# 04_2_Thermocouple_Handling_01.net
KiCad netlist of a schematic drawn in Altium Designer
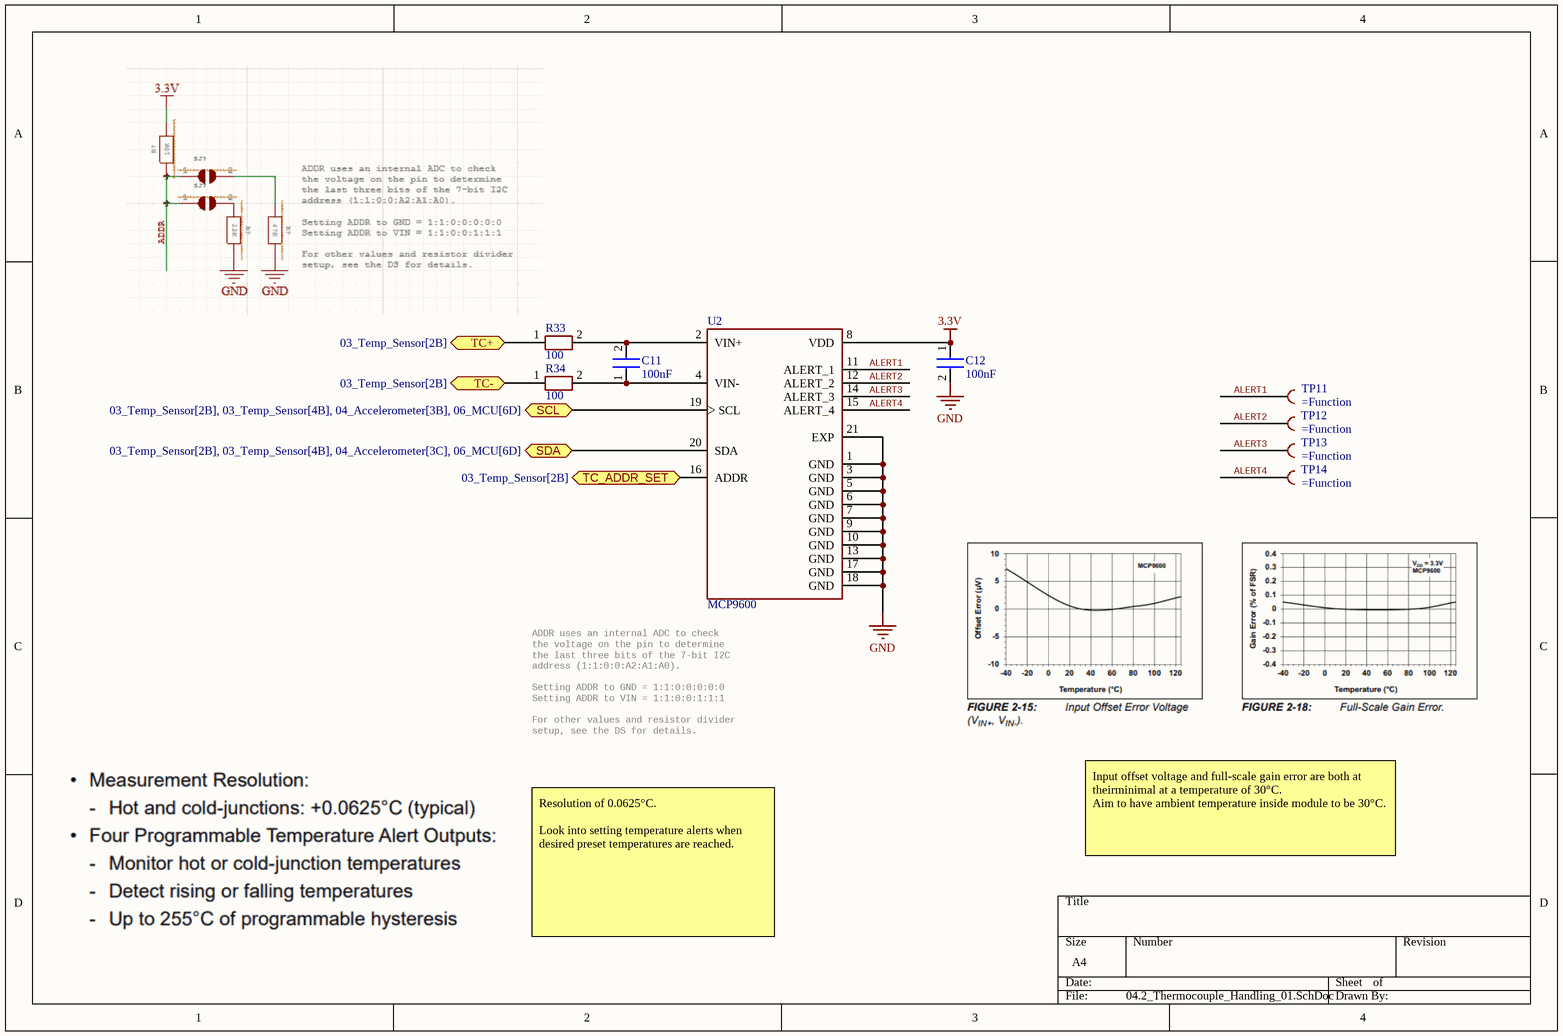
[diagram p0: 04.2_Thermocouple_Handling_01.SchDoc]

(export (version "E")
  (design (tool "Eeschema 10.0.6"))
  (components
    (comp (ref "C11")
      (value "100nF")
      (footprint "CAPC2012X94N")
      (description "Capacitor")
      (fields (field (name "MANUFACTURER_PART_NUMBER") "08055C104KAZ2A"))
      (libsource (lib "BraaiBuddyPCB_Schematic_Library") (part "CAP CER 100nF 0805 SMD"))
    )
    (comp (ref "C12")
      (value "100nF")
      (footprint "CAPC2012X94N")
      (description "Capacitor")
      (fields (field (name "MANUFACTURER_PART_NUMBER") "08055C104KAZ2A"))
      (libsource (lib "BraaiBuddyPCB_Schematic_Library") (part "CAP CER 100nF 0805 SMD"))
    )
    (comp (ref "R33")
      (value "100")
      (footprint "RESC2012X60N")
      (description "Resistor")
      (fields (field (name "MANUFACTURER_PART_NUMBER") "1623096-1"))
      (libsource (lib "BraaiBuddyPCB_Schematic_Library") (part "RES 100 0805 SMD"))
    )
    (comp (ref "R34")
      (value "100")
      (footprint "RESC2012X60N")
      (description "Resistor")
      (fields (field (name "MANUFACTURER_PART_NUMBER") "1623096-1"))
      (libsource (lib "BraaiBuddyPCB_Schematic_Library") (part "RES 100 0805 SMD"))
    )
    (comp (ref "TP11")
      (value "~")
      (footprint "TP_Pad_TH_1.2P_0.6H")
      (description "TP 1.5mm PAD")
      (libsource (lib "BraaiBuddyPCB_Schematic_Library") (part "TP 1.5mm PAD"))
    )
    (comp (ref "TP12")
      (value "~")
      (footprint "TP_Pad_TH_1.2P_0.6H")
      (description "TP 1.5mm PAD")
      (libsource (lib "BraaiBuddyPCB_Schematic_Library") (part "TP 1.5mm PAD"))
    )
    (comp (ref "TP13")
      (value "~")
      (footprint "TP_Pad_TH_1.2P_0.6H")
      (description "TP 1.5mm PAD")
      (libsource (lib "BraaiBuddyPCB_Schematic_Library") (part "TP 1.5mm PAD"))
    )
    (comp (ref "TP14")
      (value "~")
      (footprint "TP_Pad_TH_1.2P_0.6H")
      (description "TP 1.5mm PAD")
      (libsource (lib "BraaiBuddyPCB_Schematic_Library") (part "TP 1.5mm PAD"))
    )
    (comp (ref "U2")
      (value "MCP9600")
      (footprint "QFN65P500X500X100-21N")
      (description "MCP9600 Series Thermocouple Electromotive Force to Â±1.5Â°C Converter - VQFN-2")
      (fields (field (name "MANUFACTURER_PART_NUMBER") "MCP9600-E/MX"))
      (libsource (lib "BraaiBuddyPCB_Schematic_Library") (part "IC TYPE_K AMP I2Q MCP9600-I/MX SMD"))
    )
  )
  (nets
    (net (code "1") (name "/ALERT1") (class "Default")
      (node (ref "TP11") (pin "TP") (pinfunction "TP_TP") (pintype "passive"))
      (node (ref "U2") (pin "11") (pinfunction "ALERT_1_11") (pintype "passive"))
    )
    (net (code "2") (name "/ALERT2") (class "Default")
      (node (ref "TP12") (pin "TP") (pinfunction "TP_TP") (pintype "passive"))
      (node (ref "U2") (pin "12") (pinfunction "ALERT_2_12") (pintype "passive"))
    )
    (net (code "3") (name "/ALERT3") (class "Default")
      (node (ref "TP13") (pin "TP") (pinfunction "TP_TP") (pintype "passive"))
      (node (ref "U2") (pin "14") (pinfunction "ALERT_3_14") (pintype "passive"))
    )
    (net (code "4") (name "/ALERT4") (class "Default")
      (node (ref "TP14") (pin "TP") (pinfunction "TP_TP") (pintype "passive"))
      (node (ref "U2") (pin "15") (pinfunction "ALERT_4_15") (pintype "passive"))
    )
    (net (code "5") (name "/SCL") (class "Default")
      (node (ref "U2") (pin "19") (pinfunction "SCL_19") (pintype "passive"))
    )
    (net (code "6") (name "/SDA") (class "Default")
      (node (ref "U2") (pin "20") (pinfunction "SDA_20") (pintype "passive"))
    )
    (net (code "7") (name "/TC+") (class "Default")
      (node (ref "R33") (pin "1") (pinfunction "1_1") (pintype "passive"))
    )
    (net (code "8") (name "/TC-") (class "Default")
      (node (ref "R34") (pin "1") (pinfunction "1_1") (pintype "passive"))
    )
    (net (code "9") (name "/TC_ADDR_SET") (class "Default")
      (node (ref "U2") (pin "16") (pinfunction "ADDR_16") (pintype "passive"))
    )
    (net (code "10") (name "3.3V") (class "Default")
      (node (ref "C12") (pin "1") (pinfunction "1_1") (pintype "passive"))
      (node (ref "U2") (pin "8") (pinfunction "VDD_8") (pintype "passive"))
    )
    (net (code "11") (name "GND") (class "Default")
      (node (ref "C12") (pin "2") (pinfunction "2_2") (pintype "passive"))
      (node (ref "U2") (pin "1") (pinfunction "GND_1") (pintype "passive"))
      (node (ref "U2") (pin "10") (pinfunction "GND_10") (pintype "passive"))
      (node (ref "U2") (pin "13") (pinfunction "GND_13") (pintype "passive"))
      (node (ref "U2") (pin "17") (pinfunction "GND_17") (pintype "passive"))
      (node (ref "U2") (pin "18") (pinfunction "GND_18") (pintype "passive"))
      (node (ref "U2") (pin "21") (pinfunction "EXP_21") (pintype "passive"))
      (node (ref "U2") (pin "3") (pinfunction "GND_3") (pintype "passive"))
      (node (ref "U2") (pin "5") (pinfunction "GND_5") (pintype "passive"))
      (node (ref "U2") (pin "6") (pinfunction "GND_6") (pintype "passive"))
      (node (ref "U2") (pin "7") (pinfunction "GND_7") (pintype "passive"))
      (node (ref "U2") (pin "9") (pinfunction "GND_9") (pintype "passive"))
    )
    (net (code "12") (name "Net-(U2-VIN+)") (class "Default")
      (node (ref "C11") (pin "2") (pinfunction "2_2") (pintype "passive"))
      (node (ref "R33") (pin "2") (pinfunction "2_2") (pintype "passive"))
      (node (ref "U2") (pin "2") (pinfunction "VIN+_2") (pintype "passive"))
    )
    (net (code "13") (name "Net-(U2-VIN-)") (class "Default")
      (node (ref "C11") (pin "1") (pinfunction "1_1") (pintype "passive"))
      (node (ref "R34") (pin "2") (pinfunction "2_2") (pintype "passive"))
      (node (ref "U2") (pin "4") (pinfunction "VIN-_4") (pintype "passive"))
    )
  )
)
